# DC_Motor_Control.net
KiCad netlist of a schematic drawn in Altium Designer
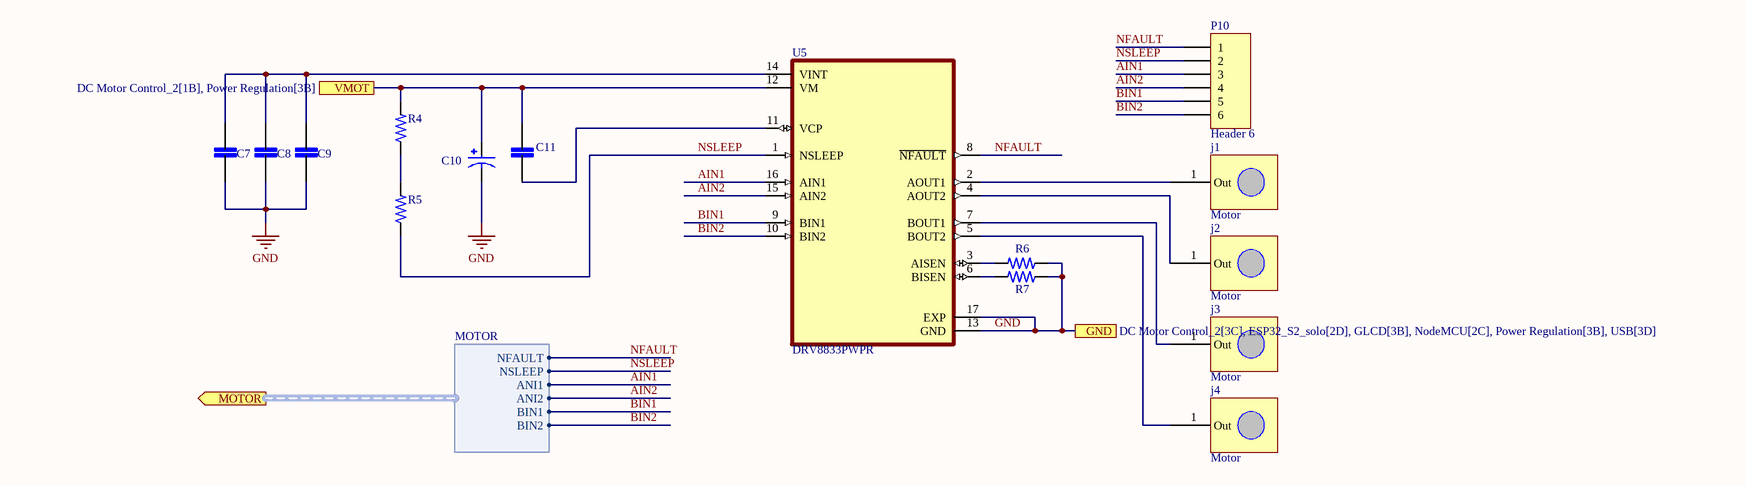
[diagram p0: DC Motor Control.SchDoc]

(export (version "E")
  (design (tool "Eeschema 10.0.6"))
  (components
    (comp (ref "C7")
      (value "LD051A121KAB2A")
      (footprint "CAPC2012X140N")
      (description "120PF 100V 10% 0805")
      (fields (field (name "MF") "{'manufacturer': u'AVX'}"))
      (libsource (lib "SnapEDA_Library") (part "LD051A121KAB2A"))
    )
    (comp (ref "C8")
      (value "LD051A121KAB2A")
      (footprint "CAPC2012X140N")
      (description "120PF 100V 10% 0805")
      (fields (field (name "MF") "{'manufacturer': u'AVX'}"))
      (libsource (lib "SnapEDA_Library") (part "LD051A121KAB2A"))
    )
    (comp (ref "C9")
      (value "LD051A121KAB2A")
      (footprint "CAPC2012X140N")
      (description "120PF 100V 10% 0805")
      (fields (field (name "MF") "{'manufacturer': u'AVX'}"))
      (libsource (lib "SnapEDA_Library") (part "LD051A121KAB2A"))
    )
    (comp (ref "C10")
      (value "EEEHA1V101UP")
      (footprint "CAP_EEEHA1V101UP")
      (fields (field (name "MF") "{'manufacturer': u'Panasonic'}"))
      (libsource (lib "SnapEDA_Library") (part "EEEHA1V101UP"))
    )
    (comp (ref "C11")
      (value "LD051A121KAB2A")
      (footprint "CAPC2012X140N")
      (description "120PF 100V 10% 0805")
      (fields (field (name "MF") "{'manufacturer': u'AVX'}"))
      (libsource (lib "SnapEDA_Library") (part "LD051A121KAB2A"))
    )
    (comp (ref "j1") (value "Motor") (footprint "Motor_pin") (libsource (lib "Schlib2") (part "Motor")))
    (comp (ref "j2") (value "Motor") (footprint "Motor_pin") (libsource (lib "Schlib2") (part "Motor")))
    (comp (ref "j3") (value "Motor") (footprint "Motor_pin") (libsource (lib "Schlib2") (part "Motor")))
    (comp (ref "j4") (value "Motor") (footprint "Motor_pin") (libsource (lib "Schlib2") (part "Motor")))
    (comp (ref "P10")
      (value "Header 6")
      (footprint "HDR1X6")
      (description "Header, 6-Pin")
      (fields (field (name "PUBLISHER") "Altium Limited"))
      (libsource (lib "Miscellaneous Connectors") (part "Header 6"))
    )
    (comp (ref "R4")
      (value "1-1879462-4")
      (footprint "RESC3115X65N")
      (description "RL73H 2B R43 1% 5K RL")
      (fields (field (name "MF") "{'manufacturer': u'TE Connectivity'}"))
      (libsource (lib "SnapEDA_Library") (part "1-1879462-4"))
    )
    (comp (ref "R5")
      (value "1-1879462-4")
      (footprint "RESC3115X65N")
      (description "RL73H 2B R43 1% 5K RL")
      (fields (field (name "MF") "{'manufacturer': u'TE Connectivity'}"))
      (libsource (lib "SnapEDA_Library") (part "1-1879462-4"))
    )
    (comp (ref "R6")
      (value "1-1879462-4")
      (footprint "RESC3115X65N")
      (description "RL73H 2B R43 1% 5K RL")
      (fields (field (name "MF") "{'manufacturer': u'TE Connectivity'}"))
      (libsource (lib "SnapEDA_Library") (part "1-1879462-4"))
    )
    (comp (ref "R7")
      (value "1-1879462-4")
      (footprint "RESC3115X65N")
      (description "RL73H 2B R43 1% 5K RL")
      (fields (field (name "MF") "{'manufacturer': u'TE Connectivity'}"))
      (libsource (lib "SnapEDA_Library") (part "1-1879462-4"))
    )
    (comp (ref "U5")
      (value "DRV8833PWPR")
      (footprint "IC_DRV8833PWPR")
      (description "10.8-V, 2-A dual H-bridge motor driver with current regulation 16-HTSSOP -40 to 85")
      (fields (field (name "MF") "{'manufacturer': u'Texas Instruments'}"))
      (libsource (lib "SnapEDA_Library") (part "DRV8833PWPR"))
    )
  )
  (nets
    (net (code "2") (name "/AIN1") (class "Default")
      (node (ref "P10") (pin "3") (pinfunction "3_3") (pintype "passive"))
      (node (ref "U5") (pin "16") (pinfunction "AIN1_16") (pintype "input"))
    )
    (net (code "3") (name "/AIN2") (class "Default")
      (node (ref "P10") (pin "4") (pinfunction "4_4") (pintype "passive"))
      (node (ref "U5") (pin "15") (pinfunction "AIN2_15") (pintype "input"))
    )
    (net (code "4") (name "/BIN1") (class "Default")
      (node (ref "P10") (pin "5") (pinfunction "5_5") (pintype "passive"))
      (node (ref "U5") (pin "9") (pinfunction "BIN1_9") (pintype "input"))
    )
    (net (code "5") (name "/BIN2") (class "Default")
      (node (ref "P10") (pin "6") (pinfunction "6_6") (pintype "passive"))
      (node (ref "U5") (pin "10") (pinfunction "BIN2_10") (pintype "input"))
    )
    (net (code "6") (name "/NFAULT") (class "Default")
      (node (ref "P10") (pin "1") (pinfunction "1_1") (pintype "passive"))
      (node (ref "U5") (pin "8") (pinfunction "~{NFAULT}_8") (pintype "output"))
    )
    (net (code "7") (name "/NSLEEP") (class "Default")
      (node (ref "P10") (pin "2") (pinfunction "2_2") (pintype "passive"))
      (node (ref "R5") (pin "1") (pinfunction "1_1") (pintype "passive"))
      (node (ref "U5") (pin "1") (pinfunction "NSLEEP_1") (pintype "input"))
    )
    (net (code "8") (name "/VMOT") (class "Default")
      (node (ref "C10") (pin "1") (pinfunction "1_1") (pintype "passive"))
      (node (ref "C11") (pin "1") (pinfunction "1_1") (pintype "passive"))
      (node (ref "R4") (pin "2") (pinfunction "2_2") (pintype "passive"))
      (node (ref "U5") (pin "12") (pinfunction "VM_12") (pintype "power_in"))
    )
    (net (code "10") (name "GND") (class "Default")
      (node (ref "C10") (pin "2") (pinfunction "2_2") (pintype "power_in"))
      (node (ref "C7") (pin "2") (pinfunction "2_2") (pintype "passive"))
      (node (ref "C8") (pin "2") (pinfunction "2_2") (pintype "passive"))
      (node (ref "C9") (pin "2") (pinfunction "2_2") (pintype "passive"))
      (node (ref "R6") (pin "1") (pinfunction "1_1") (pintype "passive"))
      (node (ref "R7") (pin "1") (pinfunction "1_1") (pintype "passive"))
      (node (ref "U5") (pin "13") (pinfunction "GND_13") (pintype "power_in"))
      (node (ref "U5") (pin "17") (pinfunction "EXP_17") (pintype "passive"))
    )
    (net (code "11") (name "Net-(R4-Pad1)") (class "Default")
      (node (ref "R4") (pin "1") (pinfunction "1_1") (pintype "passive"))
      (node (ref "R5") (pin "2") (pinfunction "2_2") (pintype "passive"))
    )
    (net (code "12") (name "Net-(U5-AISEN)") (class "Default")
      (node (ref "R6") (pin "2") (pinfunction "2_2") (pintype "passive"))
      (node (ref "U5") (pin "3") (pinfunction "AISEN_3") (pintype "bidirectional"))
    )
    (net (code "13") (name "Net-(U5-AOUT1)") (class "Default")
      (node (ref "U5") (pin "2") (pinfunction "AOUT1_2") (pintype "output"))
      (node (ref "j1") (pin "1") (pinfunction "Out_1") (pintype "passive"))
    )
    (net (code "14") (name "Net-(U5-AOUT2)") (class "Default")
      (node (ref "U5") (pin "4") (pinfunction "AOUT2_4") (pintype "output"))
      (node (ref "j2") (pin "1") (pinfunction "Out_1") (pintype "passive"))
    )
    (net (code "15") (name "Net-(U5-BISEN)") (class "Default")
      (node (ref "R7") (pin "2") (pinfunction "2_2") (pintype "passive"))
      (node (ref "U5") (pin "6") (pinfunction "BISEN_6") (pintype "bidirectional"))
    )
    (net (code "16") (name "Net-(U5-BOUT1)") (class "Default")
      (node (ref "U5") (pin "7") (pinfunction "BOUT1_7") (pintype "output"))
      (node (ref "j3") (pin "1") (pinfunction "Out_1") (pintype "passive"))
    )
    (net (code "17") (name "Net-(U5-BOUT2)") (class "Default")
      (node (ref "U5") (pin "5") (pinfunction "BOUT2_5") (pintype "output"))
      (node (ref "j4") (pin "1") (pinfunction "Out_1") (pintype "passive"))
    )
    (net (code "18") (name "Net-(U5-VCP)") (class "Default")
      (node (ref "C11") (pin "2") (pinfunction "2_2") (pintype "passive"))
      (node (ref "U5") (pin "11") (pinfunction "VCP_11") (pintype "bidirectional"))
    )
    (net (code "19") (name "Net-(U5-VINT)") (class "Default")
      (node (ref "C7") (pin "1") (pinfunction "1_1") (pintype "passive"))
      (node (ref "C8") (pin "1") (pinfunction "1_1") (pintype "passive"))
      (node (ref "C9") (pin "1") (pinfunction "1_1") (pintype "passive"))
      (node (ref "U5") (pin "14") (pinfunction "VINT_14") (pintype "power_in"))
    )
  )
)
